# Breadboard_Prototyping_Schematic.net
KiCad netlist of a schematic drawn in Altium Designer
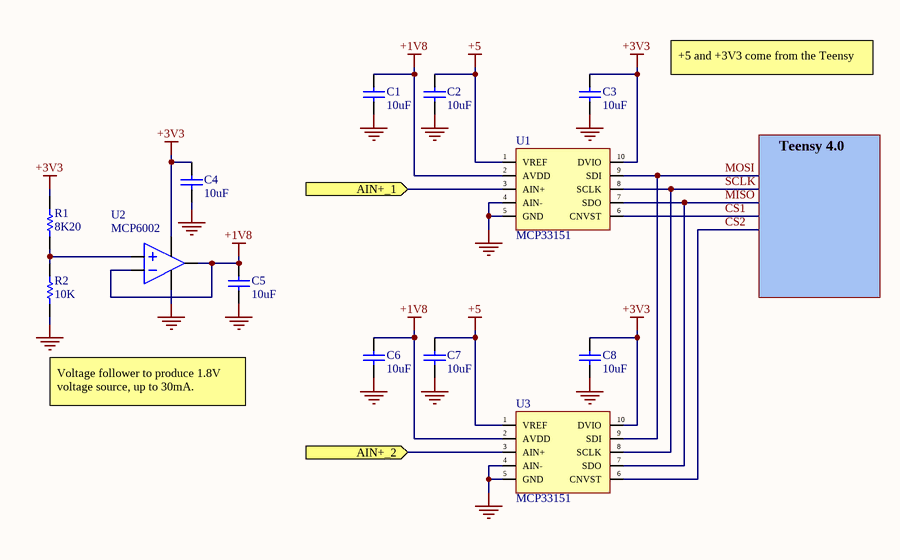
[diagram p0: Breadboard Prototyping Schematic.SchDoc]

(export (version "E")
  (design (tool "Eeschema 10.0.6"))
  (components
    (comp (ref "C1")
      (value "10uF")
      (footprint "RAD-0.3")
      (description "Capacitor")
      (fields (field (name "PUBLISHER") "Altium Limited"))
      (libsource (lib "Miscellaneous Devices") (part "Cap"))
    )
    (comp (ref "C2")
      (value "10uF")
      (footprint "RAD-0.3")
      (description "Capacitor")
      (fields (field (name "PUBLISHER") "Altium Limited"))
      (libsource (lib "Miscellaneous Devices") (part "Cap"))
    )
    (comp (ref "C3")
      (value "10uF")
      (footprint "RAD-0.3")
      (description "Capacitor")
      (fields (field (name "PUBLISHER") "Altium Limited"))
      (libsource (lib "Miscellaneous Devices") (part "Cap"))
    )
    (comp (ref "C4")
      (value "10uF")
      (footprint "RAD-0.3")
      (description "Capacitor")
      (fields (field (name "PUBLISHER") "Altium Limited"))
      (libsource (lib "Miscellaneous Devices") (part "Cap"))
    )
    (comp (ref "C5")
      (value "10uF")
      (footprint "RAD-0.3")
      (description "Capacitor")
      (fields (field (name "PUBLISHER") "Altium Limited"))
      (libsource (lib "Miscellaneous Devices") (part "Cap"))
    )
    (comp (ref "C6")
      (value "10uF")
      (footprint "RAD-0.3")
      (description "Capacitor")
      (fields (field (name "PUBLISHER") "Altium Limited"))
      (libsource (lib "Miscellaneous Devices") (part "Cap"))
    )
    (comp (ref "C7")
      (value "10uF")
      (footprint "RAD-0.3")
      (description "Capacitor")
      (fields (field (name "PUBLISHER") "Altium Limited"))
      (libsource (lib "Miscellaneous Devices") (part "Cap"))
    )
    (comp (ref "C8")
      (value "10uF")
      (footprint "RAD-0.3")
      (description "Capacitor")
      (fields (field (name "PUBLISHER") "Altium Limited"))
      (libsource (lib "Miscellaneous Devices") (part "Cap"))
    )
    (comp (ref "R1")
      (value "8K20")
      (footprint "AXIAL-0.3")
      (description "Resistor")
      (fields (field (name "PUBLISHER") "Altium Limited"))
      (libsource (lib "Miscellaneous Devices") (part "Res1"))
    )
    (comp (ref "R2")
      (value "10K")
      (footprint "AXIAL-0.3")
      (description "Resistor")
      (fields (field (name "PUBLISHER") "Altium Limited"))
      (libsource (lib "Miscellaneous Devices") (part "Res1"))
    )
    (comp (ref "U1")
      (value "MCP33151")
      (footprint "MSOP-10")
      (description "ADC 14-bit SAR 1Msps 10-MSOP")
      (fields
        (field (name "MANUFACTURER") "Microchip")
        (field (name "MANUFACTURER PART NUMBER") "MCP33151-10-E/MS")
      )
      (libsource (lib "MRT SCH Library") (part "ADC MCP33151"))
    )
    (comp (ref "U2")
      (value "MCP6002")
      (description "Generic Op Amp")
      (libsource (lib "MRT SCH Library") (part "Op Amp"))
    )
    (comp (ref "U3")
      (value "MCP33151")
      (footprint "MSOP-10")
      (description "ADC 14-bit SAR 1Msps 10-MSOP")
      (fields
        (field (name "MANUFACTURER") "Microchip")
        (field (name "MANUFACTURER PART NUMBER") "MCP33151-10-E/MS")
      )
      (libsource (lib "MRT SCH Library") (part "ADC MCP33151"))
    )
  )
  (nets
    (net (code "1") (name "+1V8") (class "Default")
      (node (ref "C1") (pin "1") (pinfunction "1_1") (pintype "passive"))
      (node (ref "C5") (pin "2") (pinfunction "2_2") (pintype "passive"))
      (node (ref "C6") (pin "1") (pinfunction "1_1") (pintype "passive"))
      (node (ref "U1") (pin "2") (pinfunction "AVDD_2") (pintype "passive"))
      (node (ref "U2") (pin "2") (pinfunction "2_2") (pintype "passive"))
      (node (ref "U2") (pin "5") (pinfunction "5_5") (pintype "passive"))
      (node (ref "U3") (pin "2") (pinfunction "AVDD_2") (pintype "passive"))
    )
    (net (code "2") (name "+3V3") (class "Default")
      (node (ref "C3") (pin "1") (pinfunction "1_1") (pintype "passive"))
      (node (ref "C4") (pin "2") (pinfunction "2_2") (pintype "passive"))
      (node (ref "C8") (pin "1") (pinfunction "1_1") (pintype "passive"))
      (node (ref "R1") (pin "2") (pinfunction "2_2") (pintype "passive"))
      (node (ref "U1") (pin "10") (pinfunction "DVIO_10") (pintype "passive"))
      (node (ref "U2") (pin "4") (pinfunction "4_4") (pintype "passive"))
      (node (ref "U3") (pin "10") (pinfunction "DVIO_10") (pintype "passive"))
    )
    (net (code "3") (name "+5") (class "Default")
      (node (ref "C2") (pin "1") (pinfunction "1_1") (pintype "passive"))
      (node (ref "C7") (pin "1") (pinfunction "1_1") (pintype "passive"))
      (node (ref "U1") (pin "1") (pinfunction "VREF_1") (pintype "passive"))
      (node (ref "U3") (pin "1") (pinfunction "VREF_1") (pintype "passive"))
    )
    (net (code "4") (name "/AIN+_1") (class "Default")
      (node (ref "U1") (pin "3") (pinfunction "AIN+_3") (pintype "passive"))
    )
    (net (code "5") (name "/AIN+_2") (class "Default")
      (node (ref "U3") (pin "3") (pinfunction "AIN+_3") (pintype "passive"))
    )
    (net (code "6") (name "/CS1") (class "Default")
      (node (ref "U1") (pin "6") (pinfunction "CNVST_6") (pintype "passive"))
    )
    (net (code "7") (name "/CS2") (class "Default")
      (node (ref "U3") (pin "6") (pinfunction "CNVST_6") (pintype "passive"))
    )
    (net (code "8") (name "/MISO") (class "Default")
      (node (ref "U1") (pin "7") (pinfunction "SDO_7") (pintype "passive"))
      (node (ref "U3") (pin "7") (pinfunction "SDO_7") (pintype "passive"))
    )
    (net (code "9") (name "/MOSI") (class "Default")
      (node (ref "U1") (pin "9") (pinfunction "SDI_9") (pintype "passive"))
      (node (ref "U3") (pin "9") (pinfunction "SDI_9") (pintype "passive"))
    )
    (net (code "10") (name "/SCLK") (class "Default")
      (node (ref "U1") (pin "8") (pinfunction "SCLK_8") (pintype "passive"))
      (node (ref "U3") (pin "8") (pinfunction "SCLK_8") (pintype "passive"))
    )
    (net (code "11") (name "GND") (class "Default")
      (node (ref "C1") (pin "2") (pinfunction "2_2") (pintype "passive"))
      (node (ref "C2") (pin "2") (pinfunction "2_2") (pintype "passive"))
      (node (ref "C3") (pin "2") (pinfunction "2_2") (pintype "passive"))
      (node (ref "C4") (pin "1") (pinfunction "1_1") (pintype "passive"))
      (node (ref "C5") (pin "1") (pinfunction "1_1") (pintype "passive"))
      (node (ref "C6") (pin "2") (pinfunction "2_2") (pintype "passive"))
      (node (ref "C7") (pin "2") (pinfunction "2_2") (pintype "passive"))
      (node (ref "C8") (pin "2") (pinfunction "2_2") (pintype "passive"))
      (node (ref "R2") (pin "1") (pinfunction "1_1") (pintype "passive"))
      (node (ref "U1") (pin "4") (pinfunction "AIN-_4") (pintype "passive"))
      (node (ref "U1") (pin "5") (pinfunction "GND_5") (pintype "passive"))
      (node (ref "U2") (pin "3") (pinfunction "3_3") (pintype "passive"))
      (node (ref "U3") (pin "4") (pinfunction "AIN-_4") (pintype "passive"))
      (node (ref "U3") (pin "5") (pinfunction "GND_5") (pintype "passive"))
    )
    (net (code "12") (name "Net-(R1-Pad1)") (class "Default")
      (node (ref "R1") (pin "1") (pinfunction "1_1") (pintype "passive"))
      (node (ref "R2") (pin "2") (pinfunction "2_2") (pintype "passive"))
      (node (ref "U2") (pin "1") (pinfunction "1_1") (pintype "passive"))
    )
  )
)
